# bare_minimum.net
KiCad netlist of a schematic drawn in EAGLE
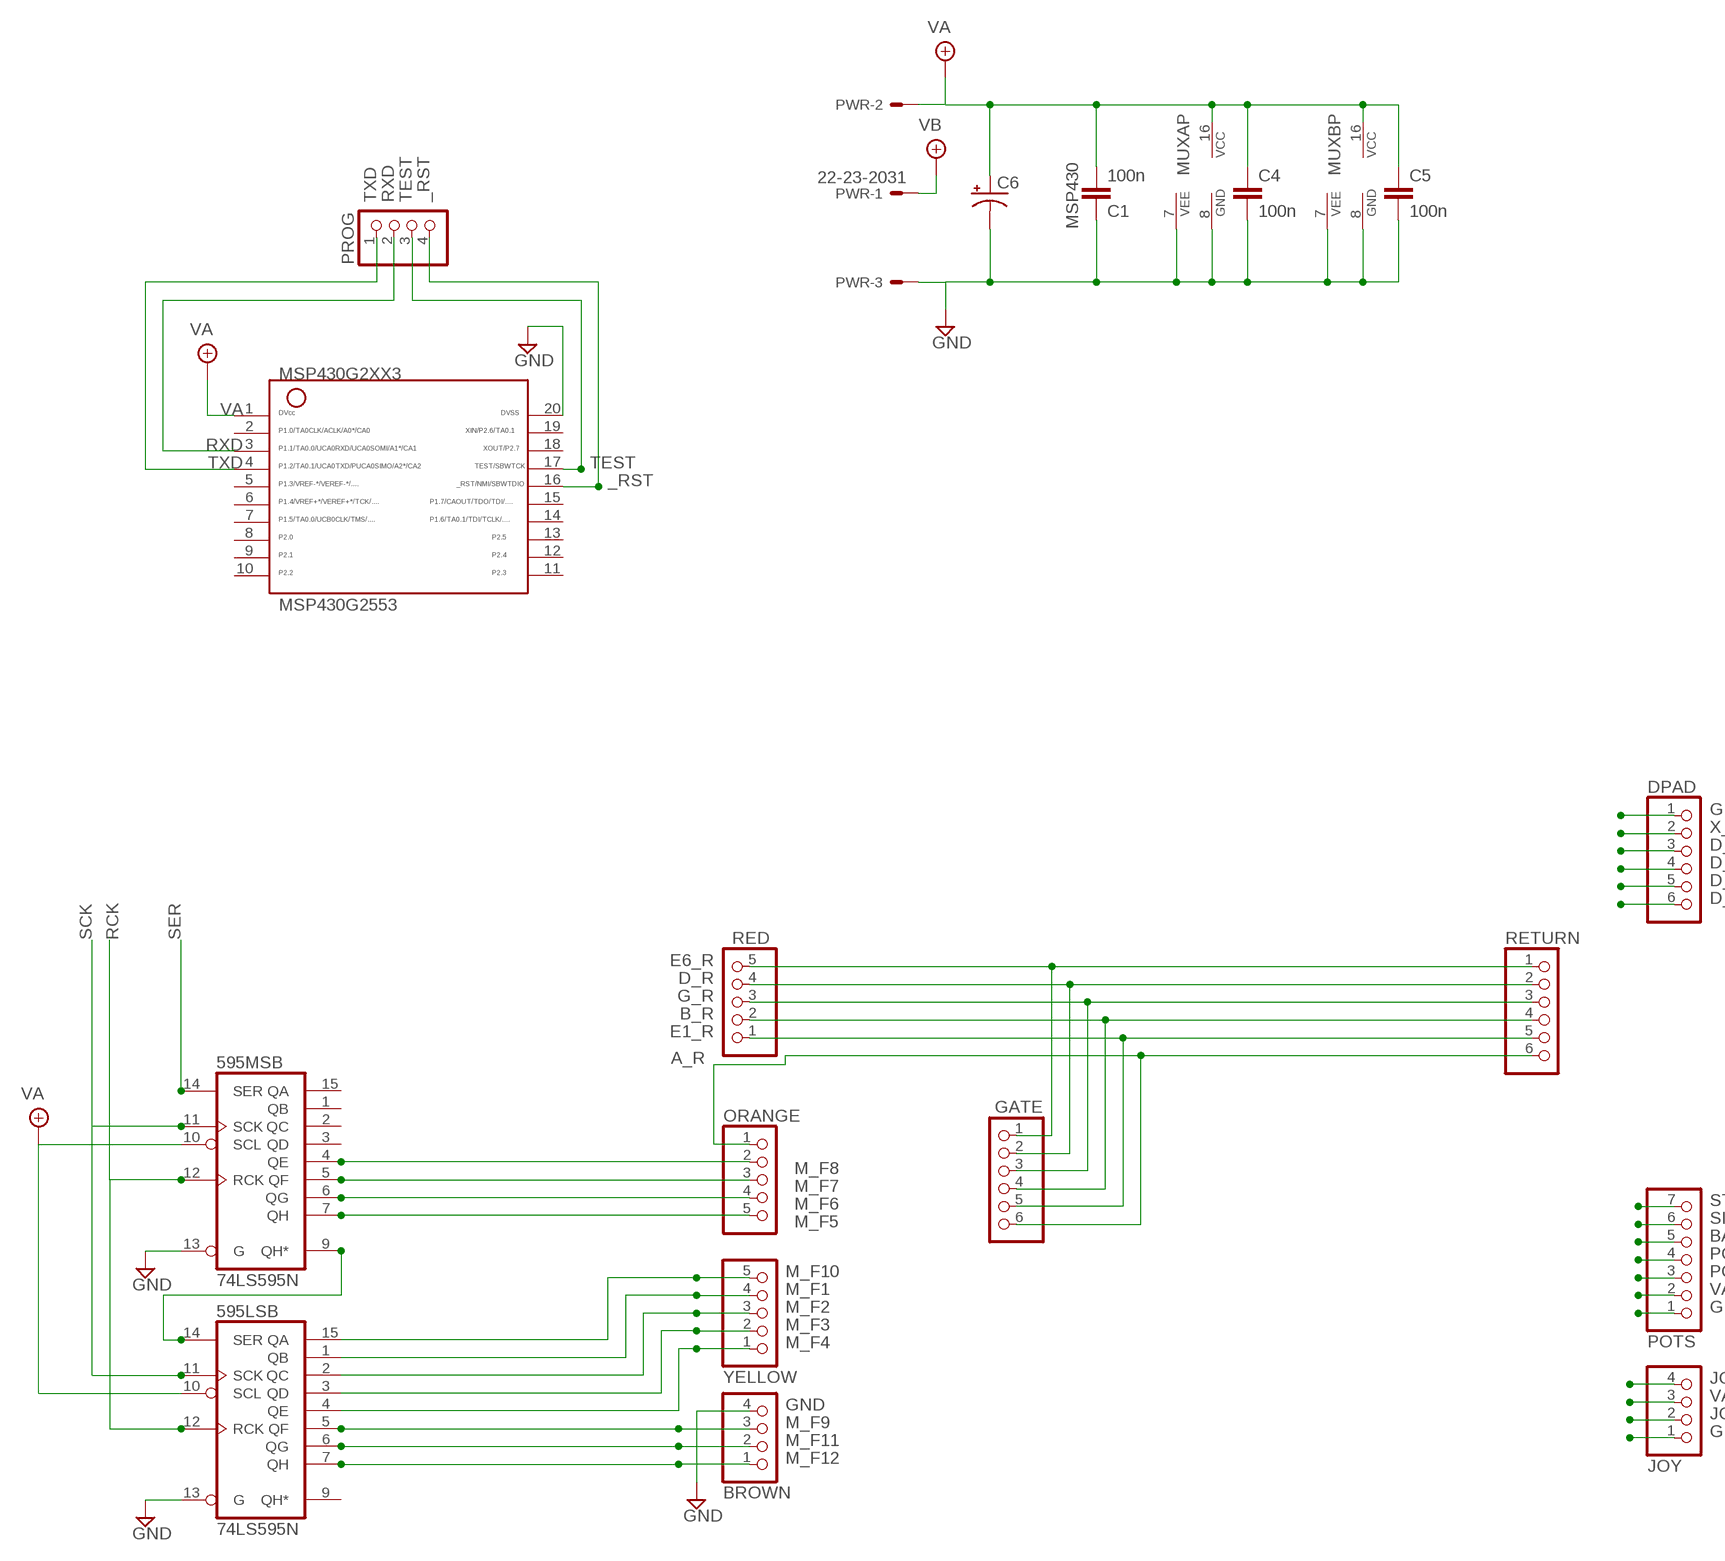
[diagram p0: schematic, sheet 1, part 1 of 2]
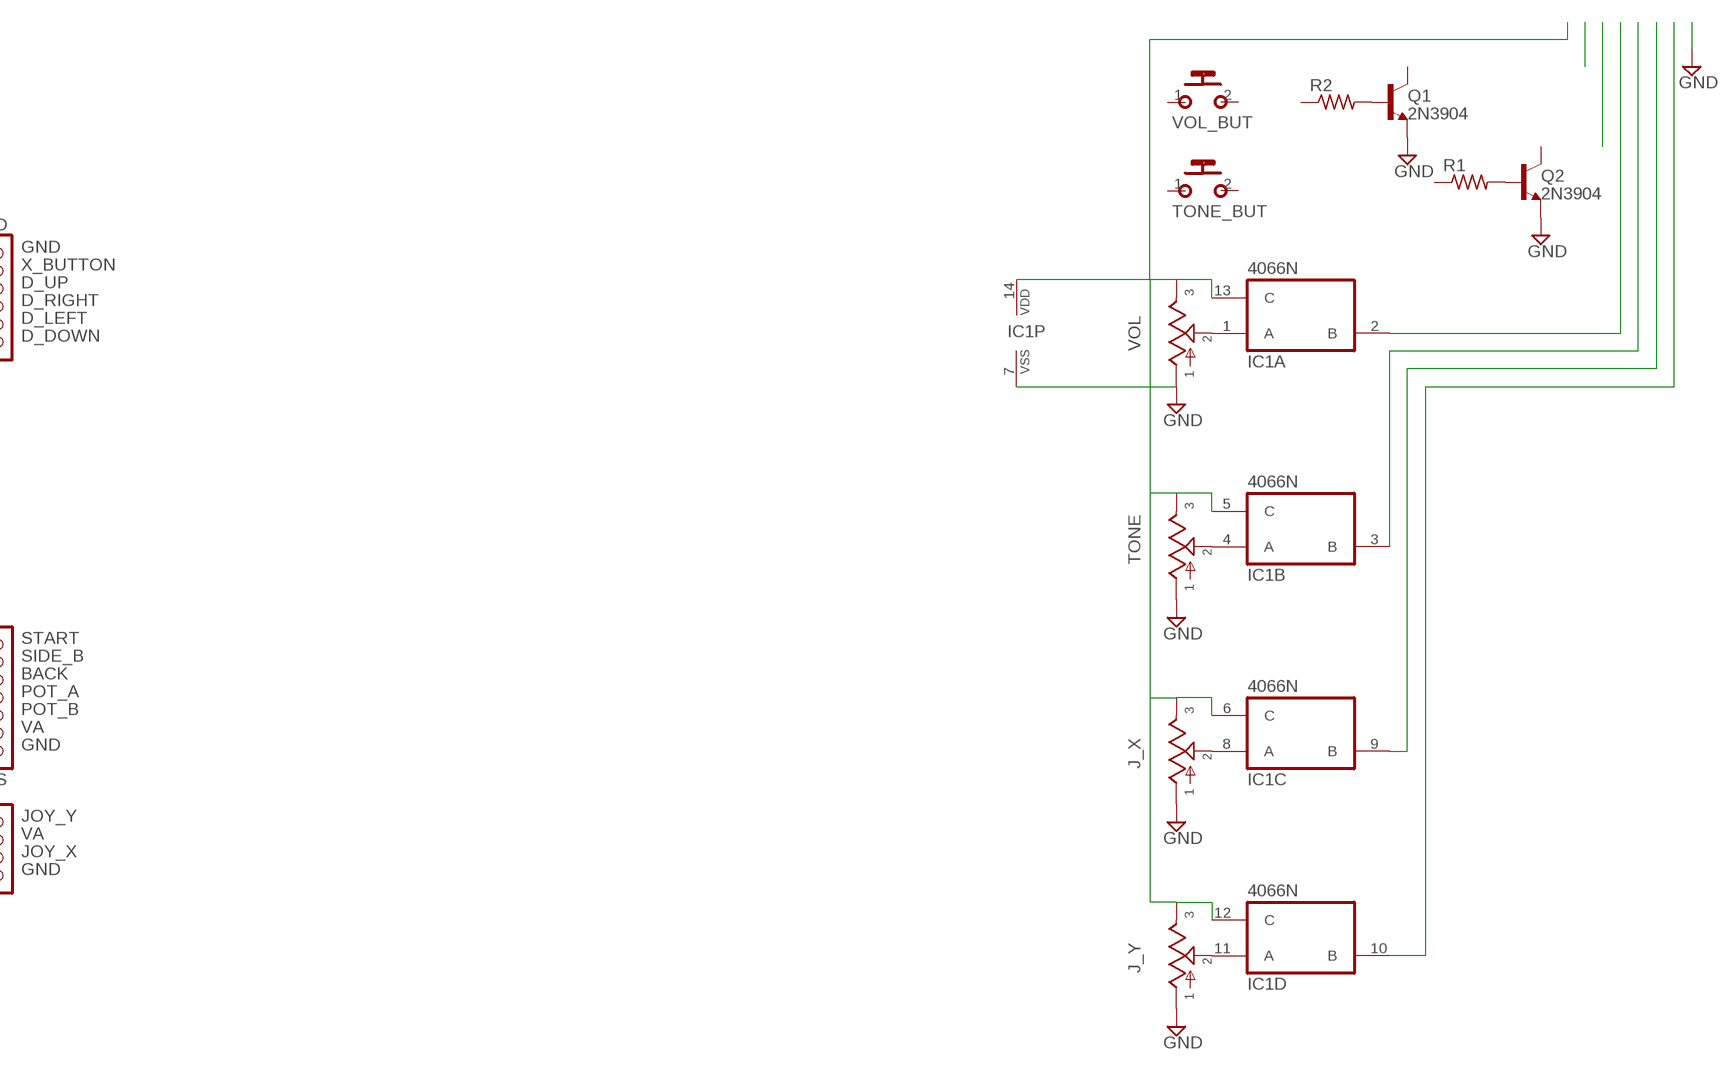
[diagram p1: schematic, sheet 1, part 2 of 2]

(export (version "E")
  (design (tool "Eeschema 10.0.6"))
  (components
    (comp (ref "595LSB")
      (value "74LS595N")
      (footprint "eagle-import:DIL16")
      (libsource (lib "eagle-import") (part "74595NLS"))
    )
    (comp (ref "595MSB")
      (value "74LS595N")
      (footprint "eagle-import:DIL16")
      (libsource (lib "eagle-import") (part "74595NLS"))
    )
    (comp (ref "BROWN")
      (value "PINHD-1X4")
      (footprint "eagle-import:1X04")
      (libsource (lib "eagle-import") (part "PINHD-1X4"))
    )
    (comp (ref "C1")
      (value "100n")
      (footprint "eagle-import:050X030_050_3")
      (libsource (lib "eagle-import") (part "050X030_050"))
    )
    (comp (ref "C4")
      (value "100n")
      (footprint "eagle-import:050X030_050_1")
      (libsource (lib "eagle-import") (part "050X030_0501"))
    )
    (comp (ref "C5")
      (value "100n")
      (footprint "eagle-import:050X030_050_3")
      (libsource (lib "eagle-import") (part "050X030_050"))
    )
    (comp (ref "C6")
      (value "0501")
      (footprint "eagle-import:050_020_1")
      (libsource (lib "eagle-import") (part "0501"))
    )
    (comp (ref "DPAD")
      (value "PINHD-1X6")
      (footprint "eagle-import:1X06")
      (libsource (lib "eagle-import") (part "PINHD-1X6"))
    )
    (comp (ref "GATE")
      (value "PINHD-1X6")
      (footprint "eagle-import:1X06")
      (libsource (lib "eagle-import") (part "PINHD-1X6"))
    )
    (comp (ref "IC1")
      (value "4066N")
      (footprint "eagle-import:DIL14")
      (libsource (lib "eagle-import") (part "4066N"))
    )
    (comp (ref "JOY")
      (value "PINHD-1X4")
      (footprint "eagle-import:1X04")
      (libsource (lib "eagle-import") (part "PINHD-1X4"))
    )
    (comp (ref "J_X")
      (value "POT16MM")
      (footprint "eagle-import:16MM")
      (libsource (lib "eagle-import") (part "POT16MM"))
    )
    (comp (ref "J_Y")
      (value "POT16MM")
      (footprint "eagle-import:16MM")
      (libsource (lib "eagle-import") (part "POT16MM"))
    )
    (comp (ref "MSP430G2553")
      (value "G2XX3---N20")
      (footprint "eagle-import:N20")
      (libsource (lib "eagle-import") (part "G2XX3---N20"))
    )
    (comp (ref "MUXA")
      (value "4051N")
      (footprint "eagle-import:DIL16")
      (libsource (lib "eagle-import") (part "4051N"))
    )
    (comp (ref "MUXB")
      (value "4052N")
      (footprint "eagle-import:DIL16")
      (libsource (lib "eagle-import") (part "4052N"))
    )
    (comp (ref "ORANGE")
      (value "PINHD-1X5")
      (footprint "eagle-import:1X05")
      (libsource (lib "eagle-import") (part "PINHD-1X5"))
    )
    (comp (ref "POTS")
      (value "PINHD-1X7")
      (footprint "eagle-import:1X07")
      (libsource (lib "eagle-import") (part "PINHD-1X7"))
    )
    (comp (ref "PROG")
      (value "PINHD-1X4")
      (footprint "eagle-import:1X04")
      (libsource (lib "eagle-import") (part "PINHD-1X4"))
    )
    (comp (ref "PWR")
      (value "22-23-2031")
      (footprint "eagle-import:22-23-2031")
      (fields (field (name "MF") "MOLEX"))
      (libsource (lib "eagle-import") (part "22-23-2031"))
    )
    (comp (ref "Q1")
      (value "2N3904")
      (footprint "eagle-import:TO92-")
      (libsource (lib "eagle-import") (part "2N3904"))
    )
    (comp (ref "Q2")
      (value "2N3904")
      (footprint "eagle-import:TO92-")
      (libsource (lib "eagle-import") (part "2N3904"))
    )
    (comp (ref "R1")
      (value "6MM.3")
      (footprint "eagle-import:R0207_3")
      (libsource (lib "eagle-import") (part "6MM.3"))
    )
    (comp (ref "R2")
      (value "6MM.3")
      (footprint "eagle-import:R0207_3")
      (libsource (lib "eagle-import") (part "6MM.3"))
    )
    (comp (ref "RED")
      (value "PINHD-1X5")
      (footprint "eagle-import:1X05")
      (libsource (lib "eagle-import") (part "PINHD-1X5"))
    )
    (comp (ref "RETURN")
      (value "PINHD-1X6")
      (footprint "eagle-import:1X06")
      (libsource (lib "eagle-import") (part "PINHD-1X6"))
    )
    (comp (ref "TONE")
      (value "POT16MM")
      (footprint "eagle-import:16MM")
      (libsource (lib "eagle-import") (part "POT16MM"))
    )
    (comp (ref "TONE_BUT")
      (value "MOMENTARY")
      (footprint "eagle-import:SPST2")
      (libsource (lib "eagle-import") (part "MOMENTARY"))
    )
    (comp (ref "VOL")
      (value "POT16MM")
      (footprint "eagle-import:16MM")
      (libsource (lib "eagle-import") (part "POT16MM"))
    )
    (comp (ref "VOL_BUT")
      (value "MOMENTARY")
      (footprint "eagle-import:SPST2")
      (libsource (lib "eagle-import") (part "MOMENTARY"))
    )
    (comp (ref "YELLOW")
      (value "PINHD-1X5")
      (footprint "eagle-import:1X05")
      (libsource (lib "eagle-import") (part "PINHD-1X5"))
    )
  )
  (nets
    (net (code "1") (name "/A_R") (class "Default")
      (node (ref "GATE") (pin "6") (pinfunction "6_6") (pintype "passive"))
      (node (ref "ORANGE") (pin "1") (pinfunction "1_1") (pintype "passive"))
      (node (ref "RETURN") (pin "6") (pinfunction "6_6") (pintype "passive"))
    )
    (net (code "2") (name "/BACK") (class "Default")
      (node (ref "POTS") (pin "7") (pinfunction "7_7") (pintype "passive"))
    )
    (net (code "3") (name "/B_R") (class "Default")
      (node (ref "GATE") (pin "4") (pinfunction "4_4") (pintype "passive"))
      (node (ref "RED") (pin "2") (pinfunction "2_2") (pintype "passive"))
      (node (ref "RETURN") (pin "4") (pinfunction "4_4") (pintype "passive"))
    )
    (net (code "4") (name "/D_DOWN") (class "Default")
      (node (ref "DPAD") (pin "6") (pinfunction "6_6") (pintype "passive"))
    )
    (net (code "5") (name "/D_LEFT") (class "Default")
      (node (ref "DPAD") (pin "5") (pinfunction "5_5") (pintype "passive"))
    )
    (net (code "6") (name "/D_R") (class "Default")
      (node (ref "GATE") (pin "2") (pinfunction "2_2") (pintype "passive"))
      (node (ref "RED") (pin "4") (pinfunction "4_4") (pintype "passive"))
      (node (ref "RETURN") (pin "2") (pinfunction "2_2") (pintype "passive"))
    )
    (net (code "7") (name "/D_RIGHT") (class "Default")
      (node (ref "DPAD") (pin "4") (pinfunction "4_4") (pintype "passive"))
    )
    (net (code "8") (name "/D_UP") (class "Default")
      (node (ref "DPAD") (pin "3") (pinfunction "3_3") (pintype "passive"))
    )
    (net (code "9") (name "/E1_R") (class "Default")
      (node (ref "GATE") (pin "5") (pinfunction "5_5") (pintype "passive"))
      (node (ref "RED") (pin "1") (pinfunction "1_1") (pintype "passive"))
      (node (ref "RETURN") (pin "5") (pinfunction "5_5") (pintype "passive"))
    )
    (net (code "10") (name "/E6_R") (class "Default")
      (node (ref "GATE") (pin "1") (pinfunction "1_1") (pintype "passive"))
      (node (ref "RED") (pin "5") (pinfunction "5_5") (pintype "passive"))
      (node (ref "RETURN") (pin "1") (pinfunction "1_1") (pintype "passive"))
    )
    (net (code "11") (name "/G_R") (class "Default")
      (node (ref "GATE") (pin "3") (pinfunction "3_3") (pintype "passive"))
      (node (ref "RED") (pin "3") (pinfunction "3_3") (pintype "passive"))
      (node (ref "RETURN") (pin "3") (pinfunction "3_3") (pintype "passive"))
    )
    (net (code "12") (name "/JOY_X") (class "Default")
      (node (ref "JOY") (pin "2") (pinfunction "2_2") (pintype "passive"))
    )
    (net (code "13") (name "/JOY_Y") (class "Default")
      (node (ref "JOY") (pin "4") (pinfunction "4_4") (pintype "passive"))
    )
    (net (code "14") (name "/M_F1") (class "Default")
      (node (ref "595LSB") (pin "1") (pinfunction "QB_1") (pintype "tri_state"))
      (node (ref "YELLOW") (pin "4") (pinfunction "4_4") (pintype "passive"))
    )
    (net (code "15") (name "/M_F2") (class "Default")
      (node (ref "595LSB") (pin "2") (pinfunction "QC_2") (pintype "tri_state"))
      (node (ref "YELLOW") (pin "3") (pinfunction "3_3") (pintype "passive"))
    )
    (net (code "16") (name "/M_F3") (class "Default")
      (node (ref "595LSB") (pin "3") (pinfunction "QD_3") (pintype "tri_state"))
      (node (ref "YELLOW") (pin "2") (pinfunction "2_2") (pintype "passive"))
    )
    (net (code "17") (name "/M_F4") (class "Default")
      (node (ref "595LSB") (pin "4") (pinfunction "QE_4") (pintype "tri_state"))
      (node (ref "YELLOW") (pin "1") (pinfunction "1_1") (pintype "passive"))
    )
    (net (code "18") (name "/M_F5") (class "Default")
      (node (ref "595MSB") (pin "7") (pinfunction "QH_7") (pintype "tri_state"))
      (node (ref "ORANGE") (pin "5") (pinfunction "5_5") (pintype "passive"))
    )
    (net (code "19") (name "/M_F6") (class "Default")
      (node (ref "595MSB") (pin "6") (pinfunction "QG_6") (pintype "tri_state"))
      (node (ref "ORANGE") (pin "4") (pinfunction "4_4") (pintype "passive"))
    )
    (net (code "20") (name "/M_F7") (class "Default")
      (node (ref "595MSB") (pin "5") (pinfunction "QF_5") (pintype "tri_state"))
      (node (ref "ORANGE") (pin "3") (pinfunction "3_3") (pintype "passive"))
    )
    (net (code "21") (name "/M_F8") (class "Default")
      (node (ref "595MSB") (pin "4") (pinfunction "QE_4") (pintype "tri_state"))
      (node (ref "ORANGE") (pin "2") (pinfunction "2_2") (pintype "passive"))
    )
    (net (code "22") (name "/M_F9") (class "Default")
      (node (ref "595LSB") (pin "5") (pinfunction "QF_5") (pintype "tri_state"))
      (node (ref "BROWN") (pin "3") (pinfunction "3_3") (pintype "passive"))
    )
    (net (code "23") (name "/M_F10") (class "Default")
      (node (ref "595LSB") (pin "15") (pinfunction "QA_15") (pintype "tri_state"))
      (node (ref "YELLOW") (pin "5") (pinfunction "5_5") (pintype "passive"))
    )
    (net (code "24") (name "/M_F11") (class "Default")
      (node (ref "595LSB") (pin "6") (pinfunction "QG_6") (pintype "tri_state"))
      (node (ref "BROWN") (pin "2") (pinfunction "2_2") (pintype "passive"))
    )
    (net (code "25") (name "/M_F12") (class "Default")
      (node (ref "595LSB") (pin "7") (pinfunction "QH_7") (pintype "tri_state"))
      (node (ref "BROWN") (pin "1") (pinfunction "1_1") (pintype "passive"))
    )
    (net (code "26") (name "/POT_A") (class "Default")
      (node (ref "POTS") (pin "4") (pinfunction "4_4") (pintype "passive"))
    )
    (net (code "27") (name "/POT_B") (class "Default")
      (node (ref "POTS") (pin "3") (pinfunction "3_3") (pintype "passive"))
    )
    (net (code "28") (name "/RCK") (class "Default")
      (node (ref "595LSB") (pin "12") (pinfunction "RCK_12") (pintype "input"))
      (node (ref "595MSB") (pin "12") (pinfunction "RCK_12") (pintype "input"))
    )
    (net (code "29") (name "/RXD") (class "Default")
      (node (ref "MSP430G2553") (pin "3") (pinfunction "3_3") (pintype "bidirectional"))
      (node (ref "PROG") (pin "2") (pinfunction "2_2") (pintype "passive"))
    )
    (net (code "30") (name "/SCK") (class "Default")
      (node (ref "595LSB") (pin "11") (pinfunction "SCK_11") (pintype "input"))
      (node (ref "595MSB") (pin "11") (pinfunction "SCK_11") (pintype "input"))
    )
    (net (code "31") (name "/SER") (class "Default")
      (node (ref "595MSB") (pin "14") (pinfunction "SER_14") (pintype "input"))
    )
    (net (code "32") (name "/SIDE_B") (class "Default")
      (node (ref "POTS") (pin "6") (pinfunction "6_6") (pintype "passive"))
    )
    (net (code "33") (name "/START") (class "Default")
      (node (ref "POTS") (pin "5") (pinfunction "5_5") (pintype "passive"))
    )
    (net (code "34") (name "/TEST") (class "Default")
      (node (ref "MSP430G2553") (pin "17") (pinfunction "17_17") (pintype "bidirectional"))
      (node (ref "PROG") (pin "3") (pinfunction "3_3") (pintype "passive"))
    )
    (net (code "35") (name "/TXD") (class "Default")
      (node (ref "MSP430G2553") (pin "4") (pinfunction "4_4") (pintype "bidirectional"))
      (node (ref "PROG") (pin "1") (pinfunction "1_1") (pintype "passive"))
    )
    (net (code "36") (name "/X_BUTTON") (class "Default")
      (node (ref "DPAD") (pin "2") (pinfunction "2_2") (pintype "passive"))
    )
    (net (code "37") (name "/_RST") (class "Default")
      (node (ref "MSP430G2553") (pin "16") (pinfunction "16_16") (pintype "bidirectional"))
      (node (ref "PROG") (pin "4") (pinfunction "4_4") (pintype "passive"))
    )
    (net (code "38") (name "GND") (class "Default")
      (node (ref "595LSB") (pin "13") (pinfunction "G_13") (pintype "input"))
      (node (ref "595MSB") (pin "13") (pinfunction "G_13") (pintype "input"))
      (node (ref "BROWN") (pin "4") (pinfunction "4_4") (pintype "passive"))
      (node (ref "C1") (pin "1") (pinfunction "1_1") (pintype "passive"))
      (node (ref "C4") (pin "2") (pinfunction "2_2") (pintype "passive"))
      (node (ref "C5") (pin "2") (pinfunction "2_2") (pintype "passive"))
      (node (ref "C6") (pin "-") (pinfunction "-_-") (pintype "passive"))
      (node (ref "DPAD") (pin "1") (pinfunction "1_1") (pintype "passive"))
      (node (ref "IC1") (pin "7") (pinfunction "VSS_7") (pintype "power_in"))
      (node (ref "JOY") (pin "1") (pinfunction "1_1") (pintype "passive"))
      (node (ref "J_X") (pin "1") (pinfunction "1_1") (pintype "passive"))
      (node (ref "J_Y") (pin "1") (pinfunction "1_1") (pintype "passive"))
      (node (ref "MSP430G2553") (pin "20") (pinfunction "20_20") (pintype "bidirectional"))
      (node (ref "MUXA") (pin "7") (pinfunction "VEE_7") (pintype "power_in"))
      (node (ref "MUXA") (pin "8") (pinfunction "GND_8") (pintype "power_in"))
      (node (ref "MUXB") (pin "7") (pinfunction "VEE_7") (pintype "power_in"))
      (node (ref "MUXB") (pin "8") (pinfunction "GND_8") (pintype "power_in"))
      (node (ref "POTS") (pin "1") (pinfunction "1_1") (pintype "passive"))
      (node (ref "PWR") (pin "3") (pinfunction "S_3") (pintype "passive"))
      (node (ref "Q1") (pin "3") (pinfunction "E_3") (pintype "passive"))
      (node (ref "Q2") (pin "3") (pinfunction "E_3") (pintype "passive"))
      (node (ref "TONE") (pin "1") (pinfunction "1_1") (pintype "passive"))
      (node (ref "VOL") (pin "1") (pinfunction "1_1") (pintype "passive"))
    )
    (net (code "39") (name "Net-(595LSBA-SER)") (class "Default")
      (node (ref "595LSB") (pin "14") (pinfunction "SER_14") (pintype "input"))
      (node (ref "595MSB") (pin "9") (pinfunction "QH*_9") (pintype "tri_state"))
    )
    (net (code "40") (name "Net-(IC1A-A)") (class "Default")
      (node (ref "IC1") (pin "1") (pinfunction "A_1") (pintype "tri_state"))
      (node (ref "VOL") (pin "2") (pinfunction "2_2") (pintype "passive"))
    )
    (net (code "41") (name "Net-(IC1A-C)") (class "Default")
      (node (ref "IC1") (pin "12") (pinfunction "C_12") (pintype "input"))
      (node (ref "IC1") (pin "13") (pinfunction "C_13") (pintype "input"))
      (node (ref "IC1") (pin "14") (pinfunction "VDD_14") (pintype "power_in"))
      (node (ref "IC1") (pin "5") (pinfunction "C_5") (pintype "input"))
      (node (ref "IC1") (pin "6") (pinfunction "C_6") (pintype "input"))
      (node (ref "J_X") (pin "3") (pinfunction "3_3") (pintype "passive"))
      (node (ref "J_Y") (pin "3") (pinfunction "3_3") (pintype "passive"))
      (node (ref "TONE") (pin "3") (pinfunction "3_3") (pintype "passive"))
      (node (ref "VOL") (pin "3") (pinfunction "3_3") (pintype "passive"))
    )
    (net (code "42") (name "Net-(IC1B-A)") (class "Default")
      (node (ref "IC1") (pin "4") (pinfunction "A_4") (pintype "tri_state"))
      (node (ref "TONE") (pin "2") (pinfunction "2_2") (pintype "passive"))
    )
    (net (code "43") (name "Net-(IC1C-A)") (class "Default")
      (node (ref "IC1") (pin "8") (pinfunction "A_8") (pintype "tri_state"))
      (node (ref "J_X") (pin "2") (pinfunction "2_2") (pintype "passive"))
    )
    (net (code "44") (name "Net-(IC1D-A)") (class "Default")
      (node (ref "IC1") (pin "11") (pinfunction "A_11") (pintype "tri_state"))
      (node (ref "J_Y") (pin "2") (pinfunction "2_2") (pintype "passive"))
    )
    (net (code "45") (name "Net-(Q1-B)") (class "Default")
      (node (ref "Q1") (pin "2") (pinfunction "B_2") (pintype "passive"))
      (node (ref "R2") (pin "2") (pinfunction "2_2") (pintype "passive"))
    )
    (net (code "46") (name "Net-(Q2-B)") (class "Default")
      (node (ref "Q2") (pin "2") (pinfunction "B_2") (pintype "passive"))
      (node (ref "R1") (pin "2") (pinfunction "2_2") (pintype "passive"))
    )
    (net (code "47") (name "VA") (class "Default")
      (node (ref "595LSB") (pin "10") (pinfunction "SCL_10") (pintype "input"))
      (node (ref "595MSB") (pin "10") (pinfunction "SCL_10") (pintype "input"))
      (node (ref "C1") (pin "2") (pinfunction "2_2") (pintype "passive"))
      (node (ref "C4") (pin "1") (pinfunction "1_1") (pintype "passive"))
      (node (ref "C5") (pin "1") (pinfunction "1_1") (pintype "passive"))
      (node (ref "C6") (pin "+") (pinfunction "+_+") (pintype "passive"))
      (node (ref "JOY") (pin "3") (pinfunction "3_3") (pintype "passive"))
      (node (ref "MSP430G2553") (pin "1") (pinfunction "1_1") (pintype "bidirectional"))
      (node (ref "MUXA") (pin "16") (pinfunction "VCC_16") (pintype "power_in"))
      (node (ref "MUXB") (pin "16") (pinfunction "VCC_16") (pintype "power_in"))
      (node (ref "POTS") (pin "2") (pinfunction "2_2") (pintype "passive"))
      (node (ref "PWR") (pin "2") (pinfunction "S_2") (pintype "passive"))
    )
    (net (code "48") (name "VB") (class "Default")
      (node (ref "PWR") (pin "1") (pinfunction "S_1") (pintype "passive"))
    )
    (net (code "49") (name "unconnected-(595LSBA-QH*-Pad9)") (class "Default")
      (node (ref "595LSB") (pin "9") (pinfunction "QH*_9") (pintype "tri_state"))
    )
    (net (code "50") (name "unconnected-(595MSBA-QA-Pad15)") (class "Default")
      (node (ref "595MSB") (pin "15") (pinfunction "QA_15") (pintype "tri_state"))
    )
    (net (code "51") (name "unconnected-(595MSBA-QB-Pad1)") (class "Default")
      (node (ref "595MSB") (pin "1") (pinfunction "QB_1") (pintype "tri_state"))
    )
    (net (code "52") (name "unconnected-(595MSBA-QC-Pad2)") (class "Default")
      (node (ref "595MSB") (pin "2") (pinfunction "QC_2") (pintype "tri_state"))
    )
    (net (code "53") (name "unconnected-(595MSBA-QD-Pad3)") (class "Default")
      (node (ref "595MSB") (pin "3") (pinfunction "QD_3") (pintype "tri_state"))
    )
    (net (code "54") (name "unconnected-(IC1A-B-Pad2)") (class "Default")
      (node (ref "IC1") (pin "2") (pinfunction "B_2") (pintype "tri_state"))
    )
    (net (code "55") (name "unconnected-(IC1B-B-Pad3)") (class "Default")
      (node (ref "IC1") (pin "3") (pinfunction "B_3") (pintype "tri_state"))
    )
    (net (code "56") (name "unconnected-(IC1C-B-Pad9)") (class "Default")
      (node (ref "IC1") (pin "9") (pinfunction "B_9") (pintype "tri_state"))
    )
    (net (code "57") (name "unconnected-(IC1D-B-Pad10)") (class "Default")
      (node (ref "IC1") (pin "10") (pinfunction "B_10") (pintype "tri_state"))
    )
    (net (code "58") (name "unconnected-(MSP430G2553-Pad2)") (class "Default")
      (node (ref "MSP430G2553") (pin "2") (pinfunction "2_2") (pintype "bidirectional"))
    )
    (net (code "59") (name "unconnected-(MSP430G2553-Pad5)") (class "Default")
      (node (ref "MSP430G2553") (pin "5") (pinfunction "5_5") (pintype "bidirectional"))
    )
    (net (code "60") (name "unconnected-(MSP430G2553-Pad6)") (class "Default")
      (node (ref "MSP430G2553") (pin "6") (pinfunction "6_6") (pintype "bidirectional"))
    )
    (net (code "61") (name "unconnected-(MSP430G2553-Pad7)") (class "Default")
      (node (ref "MSP430G2553") (pin "7") (pinfunction "7_7") (pintype "bidirectional"))
    )
    (net (code "62") (name "unconnected-(MSP430G2553-Pad8)") (class "Default")
      (node (ref "MSP430G2553") (pin "8") (pinfunction "8_8") (pintype "bidirectional"))
    )
    (net (code "63") (name "unconnected-(MSP430G2553-Pad9)") (class "Default")
      (node (ref "MSP430G2553") (pin "9") (pinfunction "9_9") (pintype "bidirectional"))
    )
    (net (code "64") (name "unconnected-(MSP430G2553-Pad10)") (class "Default")
      (node (ref "MSP430G2553") (pin "10") (pinfunction "10_10") (pintype "bidirectional"))
    )
    (net (code "65") (name "unconnected-(MSP430G2553-Pad11)") (class "Default")
      (node (ref "MSP430G2553") (pin "11") (pinfunction "11_11") (pintype "bidirectional"))
    )
    (net (code "66") (name "unconnected-(MSP430G2553-Pad12)") (class "Default")
      (node (ref "MSP430G2553") (pin "12") (pinfunction "12_12") (pintype "bidirectional"))
    )
    (net (code "67") (name "unconnected-(MSP430G2553-Pad13)") (class "Default")
      (node (ref "MSP430G2553") (pin "13") (pinfunction "13_13") (pintype "bidirectional"))
    )
    (net (code "68") (name "unconnected-(MSP430G2553-Pad14)") (class "Default")
      (node (ref "MSP430G2553") (pin "14") (pinfunction "14_14") (pintype "bidirectional"))
    )
    (net (code "69") (name "unconnected-(MSP430G2553-Pad15)") (class "Default")
      (node (ref "MSP430G2553") (pin "15") (pinfunction "15_15") (pintype "bidirectional"))
    )
    (net (code "70") (name "unconnected-(MSP430G2553-Pad18)") (class "Default")
      (node (ref "MSP430G2553") (pin "18") (pinfunction "18_18") (pintype "bidirectional"))
    )
    (net (code "71") (name "unconnected-(MSP430G2553-Pad19)") (class "Default")
      (node (ref "MSP430G2553") (pin "19") (pinfunction "19_19") (pintype "bidirectional"))
    )
    (net (code "72") (name "unconnected-(Q1-C-Pad1)") (class "Default")
      (node (ref "Q1") (pin "1") (pinfunction "C_1") (pintype "passive"))
    )
    (net (code "73") (name "unconnected-(Q2-C-Pad1)") (class "Default")
      (node (ref "Q2") (pin "1") (pinfunction "C_1") (pintype "passive"))
    )
    (net (code "74") (name "unconnected-(R1-Pad1)") (class "Default")
      (node (ref "R1") (pin "1") (pinfunction "1_1") (pintype "passive"))
    )
    (net (code "75") (name "unconnected-(R2-Pad1)") (class "Default")
      (node (ref "R2") (pin "1") (pinfunction "1_1") (pintype "passive"))
    )
    (net (code "76") (name "unconnected-(TONE_BUT-P-Pad1)") (class "Default")
      (node (ref "TONE_BUT") (pin "1") (pinfunction "P_1") (pintype "passive"))
    )
    (net (code "77") (name "unconnected-(TONE_BUT-S-Pad2)") (class "Default")
      (node (ref "TONE_BUT") (pin "2") (pinfunction "S_2") (pintype "passive"))
    )
    (net (code "78") (name "unconnected-(VOL_BUT-P-Pad1)") (class "Default")
      (node (ref "VOL_BUT") (pin "1") (pinfunction "P_1") (pintype "passive"))
    )
    (net (code "79") (name "unconnected-(VOL_BUT-S-Pad2)") (class "Default")
      (node (ref "VOL_BUT") (pin "2") (pinfunction "S_2") (pintype "passive"))
    )
  )
)
